# Octo.net
KiCad netlist of a schematic drawn in Altium Designer
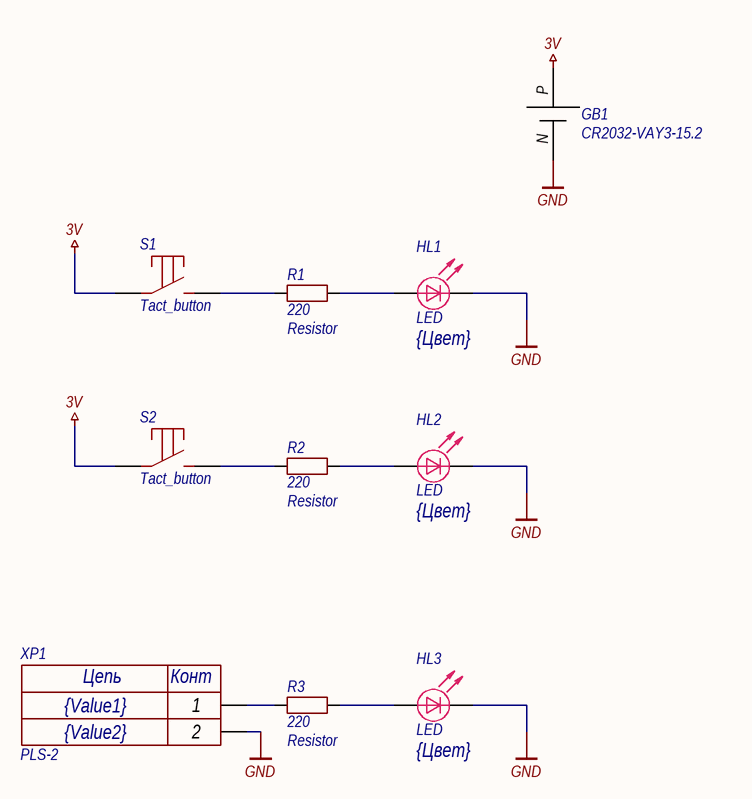
[diagram p0: Octo.SchDoc]

(export (version "E")
  (design (tool "Eeschema 10.0.6"))
  (components
    (comp (ref "GB1")
      (value "CR2032-VAY3-15.2")
      (footprint "CR2032-VAY3-15.2")
      (description "Li, MnO2 батарея типоразмера R20, 3В, 0.22Ач, приваренные выводы, -20...60 °C")
      (libsource (lib "Hydrolib") (part "Battery"))
    )
    (comp (ref "HL1")
      (value "LED")
      (footprint "3mm_led_red")
      (description "Светодиод")
      (fields (field (name "COLOR") "{Цвет}"))
      (libsource (lib "Hydrolib") (part "LED"))
    )
    (comp (ref "HL2")
      (value "LED")
      (footprint "3mm_led_red")
      (description "Светодиод")
      (fields (field (name "COLOR") "{Цвет}"))
      (libsource (lib "Hydrolib") (part "LED"))
    )
    (comp (ref "HL3")
      (value "LED")
      (footprint "3mm_led_red")
      (description "Светодиод")
      (fields (field (name "COLOR") "{Цвет}"))
      (libsource (lib "Hydrolib") (part "LED"))
    )
    (comp (ref "R1")
      (value "Resistor")
      (footprint "RES_THT_025W_220")
      (description "Резистор номиналом 220 Ом и точностью 1%")
      (fields
        (field (name "ALTIUM_VALUE") "220")
        (field (name "PART NUMBER") "Resistor_220_1_0603")
        (field (name "TOLERANCE") "1%")
      )
      (libsource (lib "Hydrolib") (part "Resistor"))
    )
    (comp (ref "R2")
      (value "Resistor")
      (footprint "RES_THT_025W_220")
      (description "Резистор номиналом 220 Ом и точностью 1%")
      (fields
        (field (name "ALTIUM_VALUE") "220")
        (field (name "PART NUMBER") "Resistor_220_1_0603")
        (field (name "TOLERANCE") "1%")
      )
      (libsource (lib "Hydrolib") (part "Resistor"))
    )
    (comp (ref "R3")
      (value "Resistor")
      (footprint "RES_THT_025W_220")
      (description "Резистор номиналом 220 Ом и точностью 1%")
      (fields
        (field (name "ALTIUM_VALUE") "220")
        (field (name "PART NUMBER") "Resistor_220_1_0603")
        (field (name "TOLERANCE") "1%")
      )
      (libsource (lib "Hydrolib") (part "Resistor"))
    )
    (comp (ref "S1")
      (value "Tact_button")
      (footprint "Button_tht_6X6")
      (description "Тактовая кнопка")
      (libsource (lib "Hydrolib") (part "Tact_button"))
    )
    (comp (ref "S2")
      (value "Tact_button")
      (footprint "Button_tht_6X6")
      (description "Тактовая кнопка")
      (libsource (lib "Hydrolib") (part "Tact_button"))
    )
    (comp (ref "XP1")
      (value "PLS-2")
      (footprint "PLS2")
      (description "Гребенка 2 пина")
      (fields (field (name "VALUE2") "{Value2}") (field (name "VALUE1") "{Value1}"))
      (libsource (lib "Hydrolib") (part "Conn_2pin"))
    )
  )
  (nets
    (net (code "1") (name "3V") (class "Default")
      (node (ref "GB1") (pin "P") (pinfunction "P_P") (pintype "passive"))
      (node (ref "S1") (pin "1") (pinfunction "1_1") (pintype "passive"))
      (node (ref "S2") (pin "1") (pinfunction "1_1") (pintype "passive"))
    )
    (net (code "2") (name "GND") (class "Default")
      (node (ref "GB1") (pin "N") (pinfunction "N_N") (pintype "passive"))
      (node (ref "HL1") (pin "2") (pinfunction "2_2") (pintype "passive"))
      (node (ref "HL2") (pin "2") (pinfunction "2_2") (pintype "passive"))
      (node (ref "HL3") (pin "2") (pinfunction "2_2") (pintype "passive"))
      (node (ref "XP1") (pin "2") (pinfunction "2_2") (pintype "passive"))
    )
    (net (code "3") (name "Net-(HL1-Pad1)") (class "Default")
      (node (ref "HL1") (pin "1") (pinfunction "1_1") (pintype "passive"))
      (node (ref "R1") (pin "2") (pinfunction "2_2") (pintype "passive"))
    )
    (net (code "4") (name "Net-(HL2-Pad1)") (class "Default")
      (node (ref "HL2") (pin "1") (pinfunction "1_1") (pintype "passive"))
      (node (ref "R2") (pin "2") (pinfunction "2_2") (pintype "passive"))
    )
    (net (code "5") (name "Net-(HL3-Pad1)") (class "Default")
      (node (ref "HL3") (pin "1") (pinfunction "1_1") (pintype "passive"))
      (node (ref "R3") (pin "2") (pinfunction "2_2") (pintype "passive"))
    )
    (net (code "6") (name "Net-(R1-Pad1)") (class "Default")
      (node (ref "R1") (pin "1") (pinfunction "1_1") (pintype "passive"))
      (node (ref "S1") (pin "2") (pinfunction "2_2") (pintype "passive"))
    )
    (net (code "7") (name "Net-(R2-Pad1)") (class "Default")
      (node (ref "R2") (pin "1") (pinfunction "1_1") (pintype "passive"))
      (node (ref "S2") (pin "2") (pinfunction "2_2") (pintype "passive"))
    )
    (net (code "8") (name "Net-(R3-Pad1)") (class "Default")
      (node (ref "R3") (pin "1") (pinfunction "1_1") (pintype "passive"))
      (node (ref "XP1") (pin "1") (pinfunction "1_1") (pintype "passive"))
    )
  )
)
